# design.net
KiCad netlist of a schematic drawn in Altium Designer
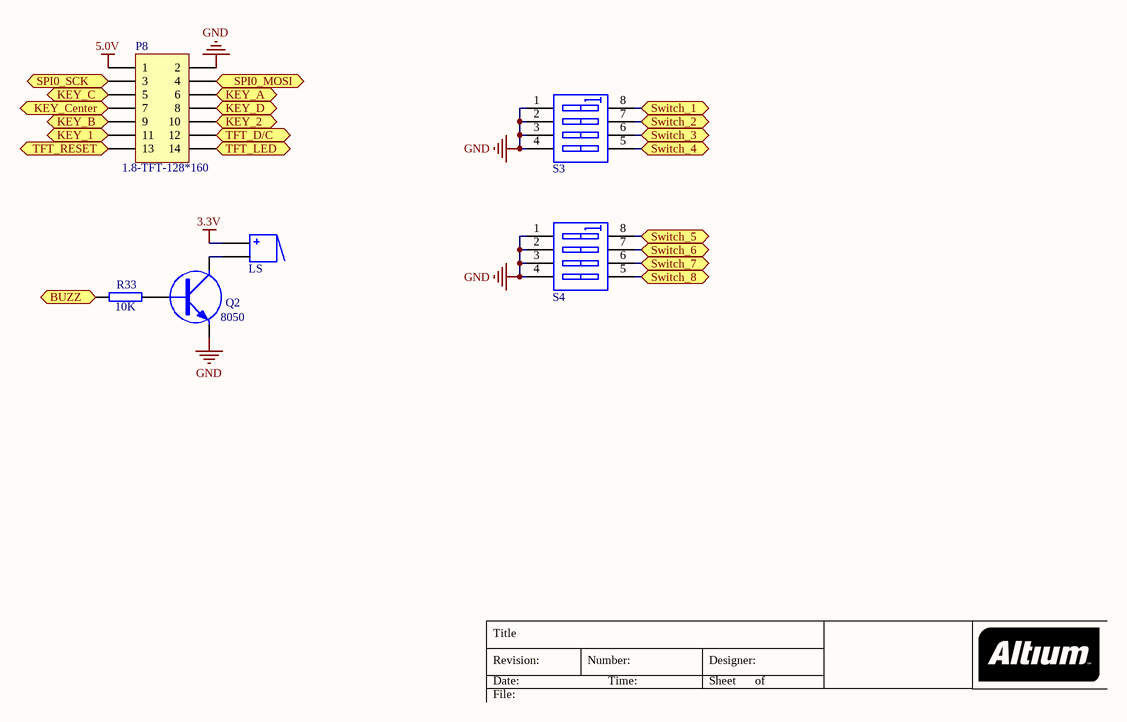
[diagram p0: 人机交互.SchDoc]

(export (version "E")
  (design (tool "Eeschema 10.0.6"))
  (components
    (comp (ref "LS")
      (value "Buzzer")
      (footprint "BUZZER_9.5*6MM")
      (libsource (lib "Connectors") (part "Buzzer"))
    )
    (comp (ref "P8")
      (value "1.8-TFT-128*160")
      (footprint "Female-Header-2.00-Double-14")
      (libsource (lib "Connectors-Header-Female") (part "CON-7X2"))
    )
    (comp (ref "Q2") (value "8050") (footprint "SOT-23-3") (libsource (lib "Devices") (part "NPN")))
    (comp (ref "R33") (value "10K") (footprint "RES-0603") (libsource (lib "Connectors") (part "Res")))
    (comp (ref "S3")
      (value "Switch")
      (footprint "SW-Piano-DIP-4")
      (libsource (lib "Connectors") (part "Switch-DIP-4"))
    )
    (comp (ref "S4")
      (value "Switch")
      (footprint "SW-Piano-DIP-4")
      (libsource (lib "Connectors") (part "Switch-DIP-4"))
    )
  )
  (nets
    (net (code "1") (name "/BUZZ") (class "Default")
      (node (ref "R33") (pin "1") (pinfunction "1_1") (pintype "passive"))
    )
    (net (code "2") (name "/KEY_1") (class "Default")
      (node (ref "P8") (pin "11") (pinfunction "11_11") (pintype "passive"))
    )
    (net (code "3") (name "/KEY_2") (class "Default")
      (node (ref "P8") (pin "10") (pinfunction "10_10") (pintype "passive"))
    )
    (net (code "4") (name "/KEY_A") (class "Default")
      (node (ref "P8") (pin "6") (pinfunction "6_6") (pintype "passive"))
    )
    (net (code "5") (name "/KEY_B") (class "Default")
      (node (ref "P8") (pin "9") (pinfunction "9_9") (pintype "passive"))
    )
    (net (code "6") (name "/KEY_C") (class "Default")
      (node (ref "P8") (pin "5") (pinfunction "5_5") (pintype "passive"))
    )
    (net (code "7") (name "/KEY_Center") (class "Default")
      (node (ref "P8") (pin "7") (pinfunction "7_7") (pintype "passive"))
    )
    (net (code "8") (name "/KEY_D") (class "Default")
      (node (ref "P8") (pin "8") (pinfunction "8_8") (pintype "passive"))
    )
    (net (code "9") (name "/SPI0_MOSI") (class "Default")
      (node (ref "P8") (pin "4") (pinfunction "4_4") (pintype "passive"))
    )
    (net (code "10") (name "/SPI0_SCK") (class "Default")
      (node (ref "P8") (pin "3") (pinfunction "3_3") (pintype "passive"))
    )
    (net (code "11") (name "/Switch_1") (class "Default")
      (node (ref "S3") (pin "8") (pinfunction "B1_8") (pintype "passive"))
    )
    (net (code "12") (name "/Switch_2") (class "Default")
      (node (ref "S3") (pin "7") (pinfunction "B2_7") (pintype "passive"))
    )
    (net (code "13") (name "/Switch_3") (class "Default")
      (node (ref "S3") (pin "6") (pinfunction "B3_6") (pintype "passive"))
    )
    (net (code "14") (name "/Switch_4") (class "Default")
      (node (ref "S3") (pin "5") (pinfunction "B4_5") (pintype "passive"))
    )
    (net (code "15") (name "/Switch_5") (class "Default")
      (node (ref "S4") (pin "8") (pinfunction "B1_8") (pintype "passive"))
    )
    (net (code "16") (name "/Switch_6") (class "Default")
      (node (ref "S4") (pin "7") (pinfunction "B2_7") (pintype "passive"))
    )
    (net (code "17") (name "/Switch_7") (class "Default")
      (node (ref "S4") (pin "6") (pinfunction "B3_6") (pintype "passive"))
    )
    (net (code "18") (name "/Switch_8") (class "Default")
      (node (ref "S4") (pin "5") (pinfunction "B4_5") (pintype "passive"))
    )
    (net (code "19") (name "/TFT_D{slash}C") (class "Default")
      (node (ref "P8") (pin "12") (pinfunction "12_12") (pintype "passive"))
    )
    (net (code "20") (name "/TFT_LED") (class "Default")
      (node (ref "P8") (pin "14") (pinfunction "14_14") (pintype "passive"))
    )
    (net (code "21") (name "/TFT_RESET") (class "Default")
      (node (ref "P8") (pin "13") (pinfunction "13_13") (pintype "passive"))
    )
    (net (code "22") (name "3.3V") (class "Default")
      (node (ref "LS") (pin "A") (pinfunction "1_A") (pintype "passive"))
    )
    (net (code "23") (name "5.0V") (class "Default")
      (node (ref "P8") (pin "1") (pinfunction "1_1") (pintype "passive"))
    )
    (net (code "24") (name "GND") (class "Default")
      (node (ref "P8") (pin "2") (pinfunction "2_2") (pintype "passive"))
      (node (ref "Q2") (pin "2") (pinfunction "E_2") (pintype "passive"))
      (node (ref "S3") (pin "1") (pinfunction "A1_1") (pintype "passive"))
      (node (ref "S3") (pin "2") (pinfunction "A2_2") (pintype "passive"))
      (node (ref "S3") (pin "3") (pinfunction "A3_3") (pintype "passive"))
      (node (ref "S3") (pin "4") (pinfunction "A4_4") (pintype "passive"))
      (node (ref "S4") (pin "1") (pinfunction "A1_1") (pintype "passive"))
      (node (ref "S4") (pin "2") (pinfunction "A2_2") (pintype "passive"))
      (node (ref "S4") (pin "3") (pinfunction "A3_3") (pintype "passive"))
      (node (ref "S4") (pin "4") (pinfunction "A4_4") (pintype "passive"))
    )
    (net (code "25") (name "Net-(LS-2)") (class "Default")
      (node (ref "LS") (pin "K") (pinfunction "2_K") (pintype "passive"))
      (node (ref "Q2") (pin "3") (pinfunction "C_3") (pintype "passive"))
    )
    (net (code "26") (name "Net-(Q2-B)") (class "Default")
      (node (ref "Q2") (pin "1") (pinfunction "B_1") (pintype "passive"))
      (node (ref "R33") (pin "2") (pinfunction "2_2") (pintype "passive"))
    )
  )
)
